# supply.net
KiCad netlist of a schematic drawn in EAGLE
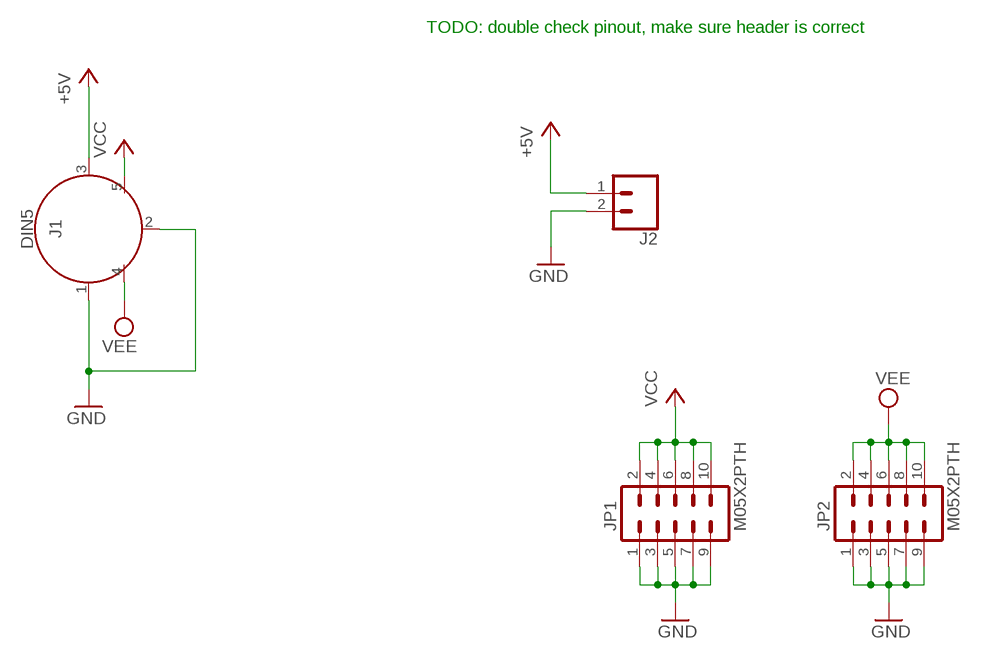
[diagram p0: schematic, sheet 1]

(export (version "E")
  (design (tool "Eeschema 10.0.6"))
  (components
    (comp (ref "J1")
      (value "DIN5")
      (footprint "eagle-import:DIN5-RA-PTH")
      (libsource (lib "eagle-import") (part "DIN5"))
    )
    (comp (ref "J2")
      (value "CONN_02")
      (footprint "eagle-import:1X02")
      (libsource (lib "eagle-import") (part "CONN_02"))
    )
    (comp (ref "JP1")
      (value "M05X2PTH")
      (footprint "eagle-import:AVR_ICSP")
      (libsource (lib "eagle-import") (part "M05X2PTH"))
    )
    (comp (ref "JP2")
      (value "M05X2PTH")
      (footprint "eagle-import:AVR_ICSP")
      (libsource (lib "eagle-import") (part "M05X2PTH"))
    )
  )
  (nets
    (net (code "1") (name "+5V") (class "Default")
      (node (ref "J1") (pin "3") (pinfunction "3_3") (pintype "bidirectional"))
      (node (ref "J2") (pin "1") (pinfunction "1_1") (pintype "passive"))
    )
    (net (code "2") (name "GND") (class "Default")
      (node (ref "J1") (pin "1") (pinfunction "1_1") (pintype "bidirectional"))
      (node (ref "J1") (pin "2") (pinfunction "2_2") (pintype "bidirectional"))
      (node (ref "J2") (pin "2") (pinfunction "2_2") (pintype "passive"))
      (node (ref "JP1") (pin "1") (pinfunction "1_1") (pintype "passive"))
      (node (ref "JP1") (pin "3") (pinfunction "3_3") (pintype "passive"))
      (node (ref "JP1") (pin "5") (pinfunction "5_5") (pintype "passive"))
      (node (ref "JP1") (pin "7") (pinfunction "7_7") (pintype "passive"))
      (node (ref "JP1") (pin "9") (pinfunction "9_9") (pintype "passive"))
      (node (ref "JP2") (pin "1") (pinfunction "1_1") (pintype "passive"))
      (node (ref "JP2") (pin "3") (pinfunction "3_3") (pintype "passive"))
      (node (ref "JP2") (pin "5") (pinfunction "5_5") (pintype "passive"))
      (node (ref "JP2") (pin "7") (pinfunction "7_7") (pintype "passive"))
      (node (ref "JP2") (pin "9") (pinfunction "9_9") (pintype "passive"))
    )
    (net (code "3") (name "VCC") (class "Default")
      (node (ref "J1") (pin "5") (pinfunction "5_5") (pintype "bidirectional"))
      (node (ref "JP1") (pin "10") (pinfunction "10_10") (pintype "passive"))
      (node (ref "JP1") (pin "2") (pinfunction "2_2") (pintype "passive"))
      (node (ref "JP1") (pin "4") (pinfunction "4_4") (pintype "passive"))
      (node (ref "JP1") (pin "6") (pinfunction "6_6") (pintype "passive"))
      (node (ref "JP1") (pin "8") (pinfunction "8_8") (pintype "passive"))
    )
    (net (code "4") (name "VEE") (class "Default")
      (node (ref "J1") (pin "4") (pinfunction "4_4") (pintype "bidirectional"))
      (node (ref "JP2") (pin "10") (pinfunction "10_10") (pintype "passive"))
      (node (ref "JP2") (pin "2") (pinfunction "2_2") (pintype "passive"))
      (node (ref "JP2") (pin "4") (pinfunction "4_4") (pintype "passive"))
      (node (ref "JP2") (pin "6") (pinfunction "6_6") (pintype "passive"))
      (node (ref "JP2") (pin "8") (pinfunction "8_8") (pintype "passive"))
    )
  )
)
